# CAN.net
KiCad netlist of a schematic drawn in Altium Designer
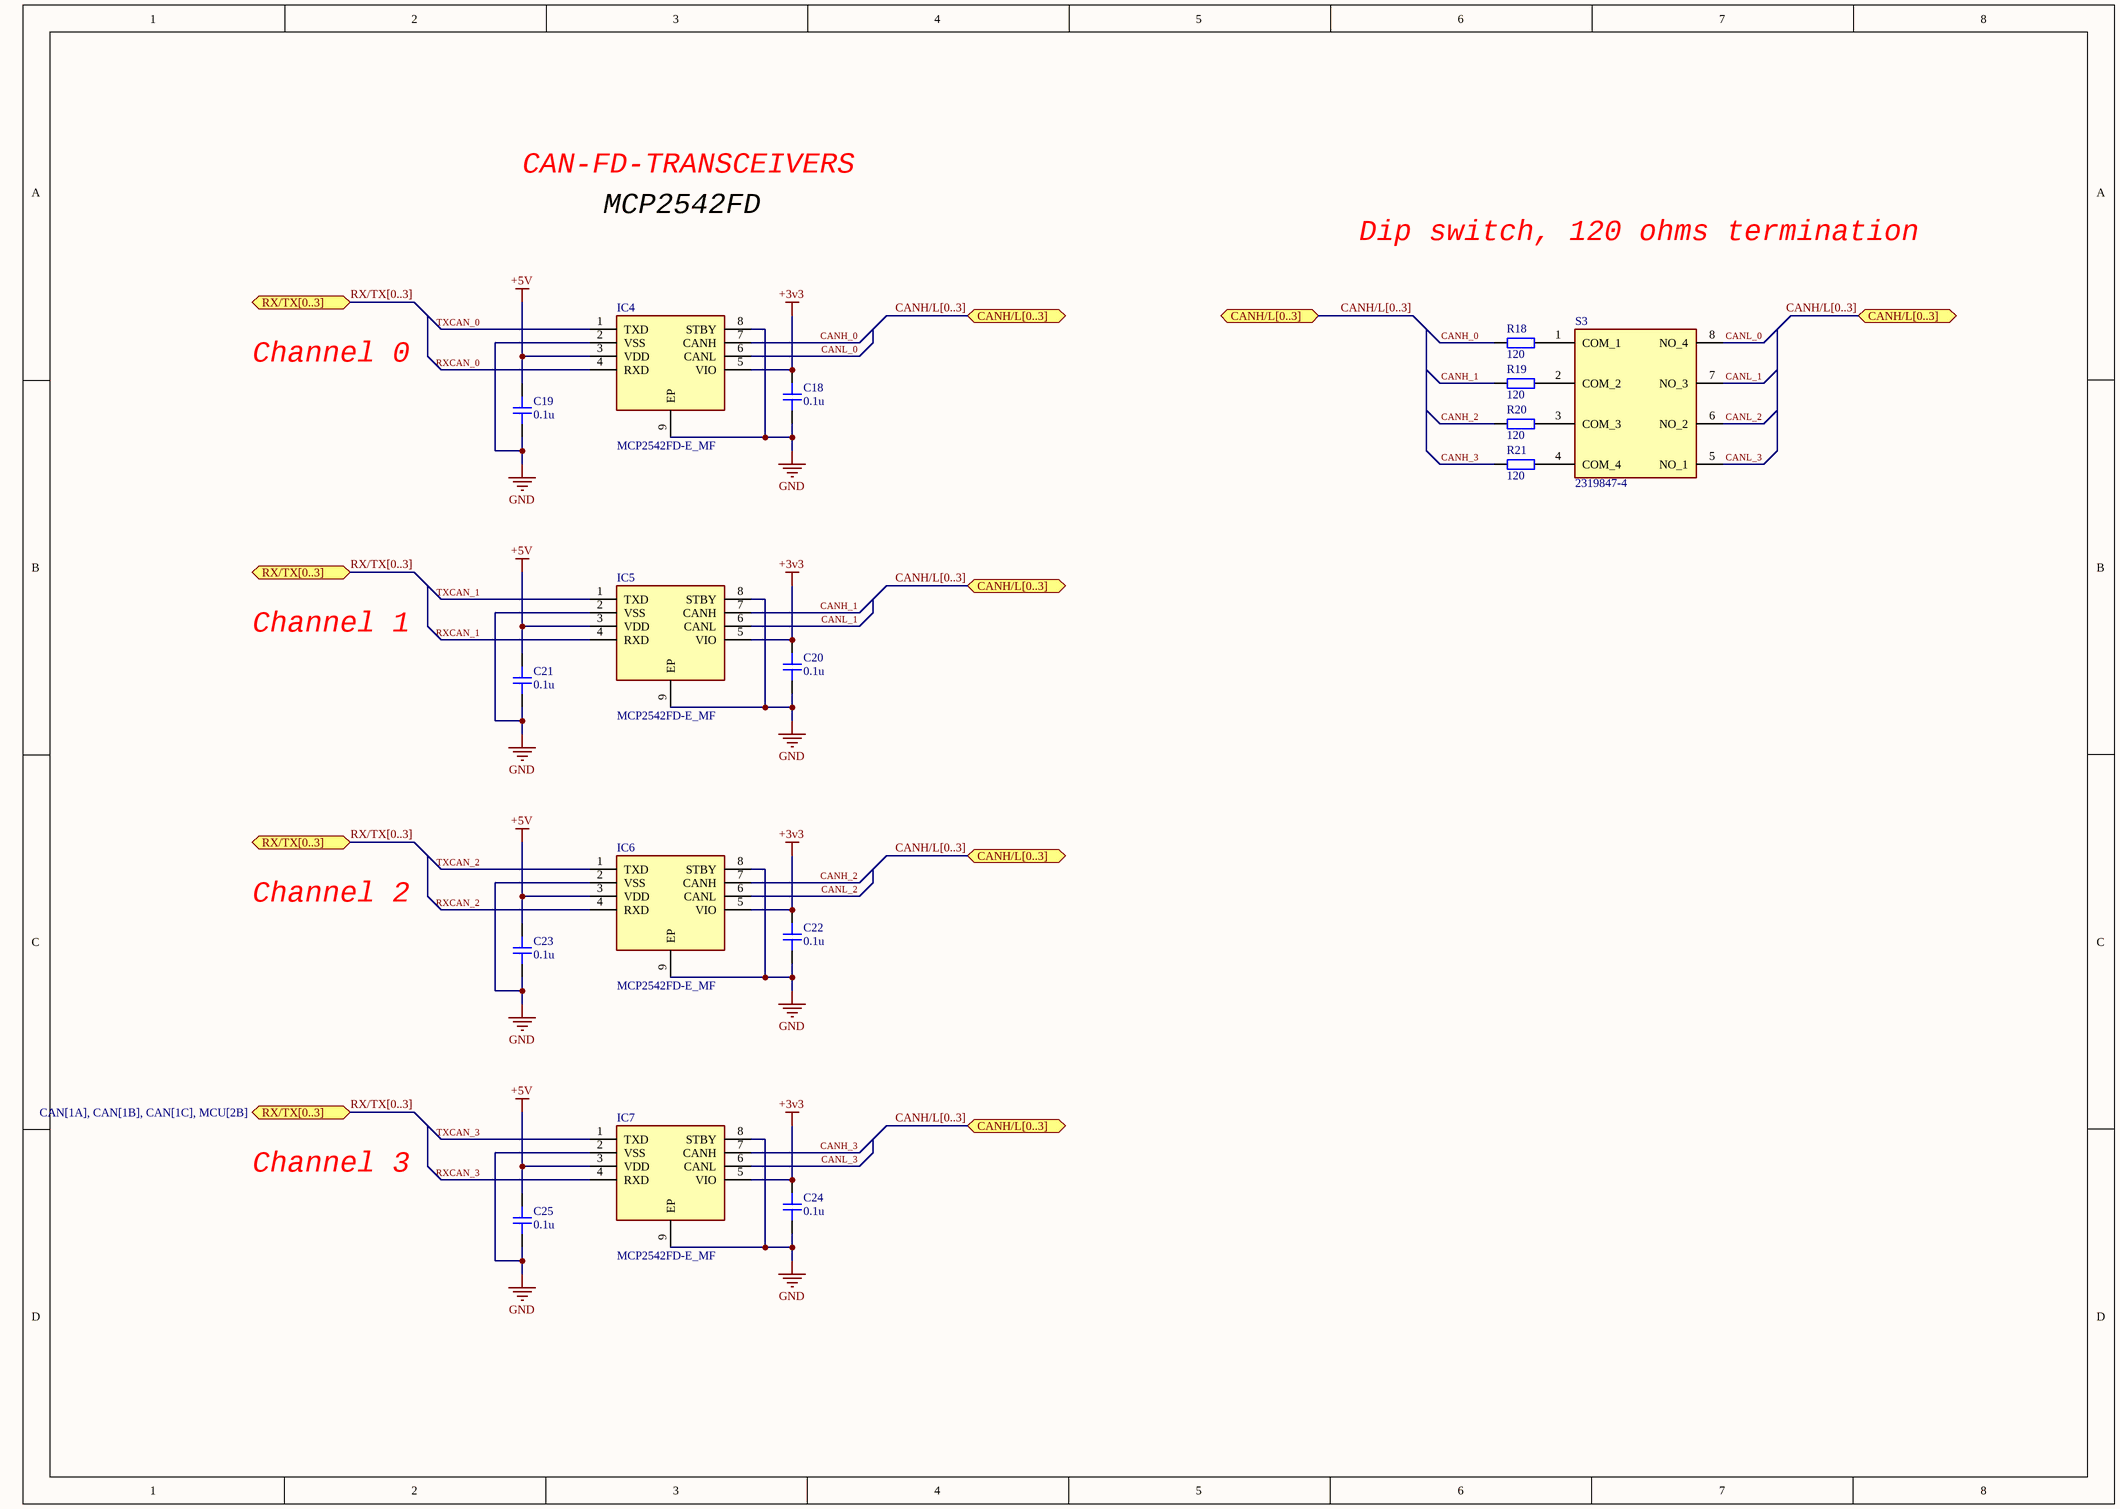
[diagram p0: CAN.SchDoc]

(export (version "E")
  (design (tool "Eeschema 10.0.6"))
  (components
    (comp (ref "C18")
      (value "0.1u")
      (footprint "CAP_0805")
      (description "Capacitor SMD 0805 10V")
      (libsource (lib "Schematic-Lib-PhilsLab") (part "CAP_0805_10V"))
    )
    (comp (ref "C19")
      (value "0.1u")
      (footprint "CAP_0805")
      (description "Capacitor SMD 0805 10V")
      (libsource (lib "Schematic-Lib-PhilsLab") (part "CAP_0805_10V"))
    )
    (comp (ref "C20")
      (value "0.1u")
      (footprint "CAP_0805")
      (description "Capacitor SMD 0805 10V")
      (libsource (lib "Schematic-Lib-PhilsLab") (part "CAP_0805_10V"))
    )
    (comp (ref "C21")
      (value "0.1u")
      (footprint "CAP_0805")
      (description "Capacitor SMD 0805 10V")
      (libsource (lib "Schematic-Lib-PhilsLab") (part "CAP_0805_10V"))
    )
    (comp (ref "C22")
      (value "0.1u")
      (footprint "CAP_0805")
      (description "Capacitor SMD 0805 10V")
      (libsource (lib "Schematic-Lib-PhilsLab") (part "CAP_0805_10V"))
    )
    (comp (ref "C23")
      (value "0.1u")
      (footprint "CAP_0805")
      (description "Capacitor SMD 0805 10V")
      (libsource (lib "Schematic-Lib-PhilsLab") (part "CAP_0805_10V"))
    )
    (comp (ref "C24")
      (value "0.1u")
      (footprint "CAP_0805")
      (description "Capacitor SMD 0805 10V")
      (libsource (lib "Schematic-Lib-PhilsLab") (part "CAP_0805_10V"))
    )
    (comp (ref "C25")
      (value "0.1u")
      (footprint "CAP_0805")
      (description "Capacitor SMD 0805 10V")
      (libsource (lib "Schematic-Lib-PhilsLab") (part "CAP_0805_10V"))
    )
    (comp (ref "IC4")
      (value "MCP2542FD-E_MF")
      (footprint "Pedro_pcb_lib:SON65P300X300X100-9N-D")
      (description "Integrated Circuit")
      (fields
        (field (name "MANUFACTURER_PART_NUMBER") "MCP2542FD-E/MF")
        (field (name "MOUSER PART NUMBER") "579-MCP2542FD-E/MF")
      )
      (libsource (lib "*") (part "MCP2542FD-E_MF"))
    )
    (comp (ref "IC5")
      (value "MCP2542FD-E_MF")
      (footprint "Pedro_pcb_lib:SON65P300X300X100-9N-D")
      (description "Integrated Circuit")
      (fields
        (field (name "MANUFACTURER_PART_NUMBER") "MCP2542FD-E/MF")
        (field (name "MOUSER PART NUMBER") "579-MCP2542FD-E/MF")
      )
      (libsource (lib "*") (part "MCP2542FD-E_MF"))
    )
    (comp (ref "IC6")
      (value "MCP2542FD-E_MF")
      (footprint "Pedro_pcb_lib:SON65P300X300X100-9N-D")
      (description "Integrated Circuit")
      (fields
        (field (name "MANUFACTURER_PART_NUMBER") "MCP2542FD-E/MF")
        (field (name "MOUSER PART NUMBER") "579-MCP2542FD-E/MF")
      )
      (libsource (lib "*") (part "MCP2542FD-E_MF"))
    )
    (comp (ref "IC7")
      (value "MCP2542FD-E_MF")
      (footprint "Pedro_pcb_lib:SON65P300X300X100-9N-D")
      (description "Integrated Circuit")
      (fields
        (field (name "MANUFACTURER_PART_NUMBER") "MCP2542FD-E/MF")
        (field (name "MOUSER PART NUMBER") "579-MCP2542FD-E/MF")
      )
      (libsource (lib "*") (part "MCP2542FD-E_MF"))
    )
    (comp (ref "R18")
      (value "120")
      (footprint "RES_0805")
      (description "Resistor SMD 0805")
      (libsource (lib "Pedro_Integrated_Library") (part "RES_0805"))
    )
    (comp (ref "R19")
      (value "120")
      (footprint "RES_0805")
      (description "Resistor SMD 0805")
      (libsource (lib "Pedro_Integrated_Library") (part "RES_0805"))
    )
    (comp (ref "R20")
      (value "120")
      (footprint "RES_0805")
      (description "Resistor SMD 0805")
      (libsource (lib "Pedro_Integrated_Library") (part "RES_0805"))
    )
    (comp (ref "R21")
      (value "120")
      (footprint "RES_0805")
      (description "Resistor SMD 0805")
      (libsource (lib "Pedro_Integrated_Library") (part "RES_0805"))
    )
    (comp (ref "S3")
      (value "2319847-4")
      (footprint "23198474")
      (description "Switch")
      (libsource (lib "Pedro_Integrated_Library") (part "2319847-4"))
    )
  )
  (nets
    (net (code "9") (name "+3v3") (class "Default")
      (node (ref "C18") (pin "2") (pinfunction "2_2") (pintype "passive"))
      (node (ref "C20") (pin "2") (pinfunction "2_2") (pintype "passive"))
      (node (ref "C22") (pin "2") (pinfunction "2_2") (pintype "passive"))
      (node (ref "C24") (pin "2") (pinfunction "2_2") (pintype "passive"))
      (node (ref "IC4") (pin "5") (pinfunction "VIO_5") (pintype "passive"))
      (node (ref "IC5") (pin "5") (pinfunction "VIO_5") (pintype "passive"))
      (node (ref "IC6") (pin "5") (pinfunction "VIO_5") (pintype "passive"))
      (node (ref "IC7") (pin "5") (pinfunction "VIO_5") (pintype "passive"))
    )
    (net (code "10") (name "+5V") (class "Default")
      (node (ref "C19") (pin "2") (pinfunction "2_2") (pintype "passive"))
      (node (ref "C21") (pin "2") (pinfunction "2_2") (pintype "passive"))
      (node (ref "C23") (pin "2") (pinfunction "2_2") (pintype "passive"))
      (node (ref "C25") (pin "2") (pinfunction "2_2") (pintype "passive"))
      (node (ref "IC4") (pin "3") (pinfunction "VDD_3") (pintype "passive"))
      (node (ref "IC5") (pin "3") (pinfunction "VDD_3") (pintype "passive"))
      (node (ref "IC6") (pin "3") (pinfunction "VDD_3") (pintype "passive"))
      (node (ref "IC7") (pin "3") (pinfunction "VDD_3") (pintype "passive"))
    )
    (net (code "11") (name "/CANH_0") (class "Default")
      (node (ref "IC4") (pin "7") (pinfunction "CANH_7") (pintype "passive"))
      (node (ref "R18") (pin "1") (pinfunction "1_1") (pintype "passive"))
    )
    (net (code "12") (name "/CANH_1") (class "Default")
      (node (ref "IC5") (pin "7") (pinfunction "CANH_7") (pintype "passive"))
      (node (ref "R19") (pin "1") (pinfunction "1_1") (pintype "passive"))
    )
    (net (code "13") (name "/CANH_2") (class "Default")
      (node (ref "IC6") (pin "7") (pinfunction "CANH_7") (pintype "passive"))
      (node (ref "R20") (pin "1") (pinfunction "1_1") (pintype "passive"))
    )
    (net (code "14") (name "/CANH_3") (class "Default")
      (node (ref "IC7") (pin "7") (pinfunction "CANH_7") (pintype "passive"))
      (node (ref "R21") (pin "1") (pinfunction "1_1") (pintype "passive"))
    )
    (net (code "16") (name "/CANL_0") (class "Default")
      (node (ref "IC4") (pin "6") (pinfunction "CANL_6") (pintype "passive"))
      (node (ref "S3") (pin "8") (pinfunction "NO_4_8") (pintype "passive"))
    )
    (net (code "17") (name "/CANL_1") (class "Default")
      (node (ref "IC5") (pin "6") (pinfunction "CANL_6") (pintype "passive"))
      (node (ref "S3") (pin "7") (pinfunction "NO_3_7") (pintype "passive"))
    )
    (net (code "18") (name "/CANL_2") (class "Default")
      (node (ref "IC6") (pin "6") (pinfunction "CANL_6") (pintype "passive"))
      (node (ref "S3") (pin "6") (pinfunction "NO_2_6") (pintype "passive"))
    )
    (net (code "19") (name "/CANL_3") (class "Default")
      (node (ref "IC7") (pin "6") (pinfunction "CANL_6") (pintype "passive"))
      (node (ref "S3") (pin "5") (pinfunction "NO_1_5") (pintype "passive"))
    )
    (net (code "20") (name "/RXCAN_0") (class "Default")
      (node (ref "IC4") (pin "4") (pinfunction "RXD_4") (pintype "passive"))
    )
    (net (code "21") (name "/RXCAN_1") (class "Default")
      (node (ref "IC5") (pin "4") (pinfunction "RXD_4") (pintype "passive"))
    )
    (net (code "22") (name "/RXCAN_2") (class "Default")
      (node (ref "IC6") (pin "4") (pinfunction "RXD_4") (pintype "passive"))
    )
    (net (code "23") (name "/RXCAN_3") (class "Default")
      (node (ref "IC7") (pin "4") (pinfunction "RXD_4") (pintype "passive"))
    )
    (net (code "25") (name "/TXCAN_0") (class "Default")
      (node (ref "IC4") (pin "1") (pinfunction "TXD_1") (pintype "passive"))
    )
    (net (code "26") (name "/TXCAN_1") (class "Default")
      (node (ref "IC5") (pin "1") (pinfunction "TXD_1") (pintype "passive"))
    )
    (net (code "27") (name "/TXCAN_2") (class "Default")
      (node (ref "IC6") (pin "1") (pinfunction "TXD_1") (pintype "passive"))
    )
    (net (code "28") (name "/TXCAN_3") (class "Default")
      (node (ref "IC7") (pin "1") (pinfunction "TXD_1") (pintype "passive"))
    )
    (net (code "29") (name "GND") (class "Default")
      (node (ref "C18") (pin "1") (pinfunction "1_1") (pintype "passive"))
      (node (ref "C19") (pin "1") (pinfunction "1_1") (pintype "passive"))
      (node (ref "C20") (pin "1") (pinfunction "1_1") (pintype "passive"))
      (node (ref "C21") (pin "1") (pinfunction "1_1") (pintype "passive"))
      (node (ref "C22") (pin "1") (pinfunction "1_1") (pintype "passive"))
      (node (ref "C23") (pin "1") (pinfunction "1_1") (pintype "passive"))
      (node (ref "C24") (pin "1") (pinfunction "1_1") (pintype "passive"))
      (node (ref "C25") (pin "1") (pinfunction "1_1") (pintype "passive"))
      (node (ref "IC4") (pin "2") (pinfunction "VSS_2") (pintype "passive"))
      (node (ref "IC4") (pin "8") (pinfunction "STBY_8") (pintype "passive"))
      (node (ref "IC4") (pin "9") (pinfunction "EP_9") (pintype "passive"))
      (node (ref "IC5") (pin "2") (pinfunction "VSS_2") (pintype "passive"))
      (node (ref "IC5") (pin "8") (pinfunction "STBY_8") (pintype "passive"))
      (node (ref "IC5") (pin "9") (pinfunction "EP_9") (pintype "passive"))
      (node (ref "IC6") (pin "2") (pinfunction "VSS_2") (pintype "passive"))
      (node (ref "IC6") (pin "8") (pinfunction "STBY_8") (pintype "passive"))
      (node (ref "IC6") (pin "9") (pinfunction "EP_9") (pintype "passive"))
      (node (ref "IC7") (pin "2") (pinfunction "VSS_2") (pintype "passive"))
      (node (ref "IC7") (pin "8") (pinfunction "STBY_8") (pintype "passive"))
      (node (ref "IC7") (pin "9") (pinfunction "EP_9") (pintype "passive"))
    )
    (net (code "30") (name "Net-(S3-COM_1)") (class "Default")
      (node (ref "R18") (pin "2") (pinfunction "2_2") (pintype "passive"))
      (node (ref "S3") (pin "1") (pinfunction "COM_1_1") (pintype "passive"))
    )
    (net (code "31") (name "Net-(S3-COM_2)") (class "Default")
      (node (ref "R19") (pin "2") (pinfunction "2_2") (pintype "passive"))
      (node (ref "S3") (pin "2") (pinfunction "COM_2_2") (pintype "passive"))
    )
    (net (code "32") (name "Net-(S3-COM_3)") (class "Default")
      (node (ref "R20") (pin "2") (pinfunction "2_2") (pintype "passive"))
      (node (ref "S3") (pin "3") (pinfunction "COM_3_3") (pintype "passive"))
    )
    (net (code "33") (name "Net-(S3-COM_4)") (class "Default")
      (node (ref "R21") (pin "2") (pinfunction "2_2") (pintype "passive"))
      (node (ref "S3") (pin "4") (pinfunction "COM_4_4") (pintype "passive"))
    )
  )
)
